# Telemetry_temp_meas.net
KiCad netlist of a schematic drawn in Altium Designer
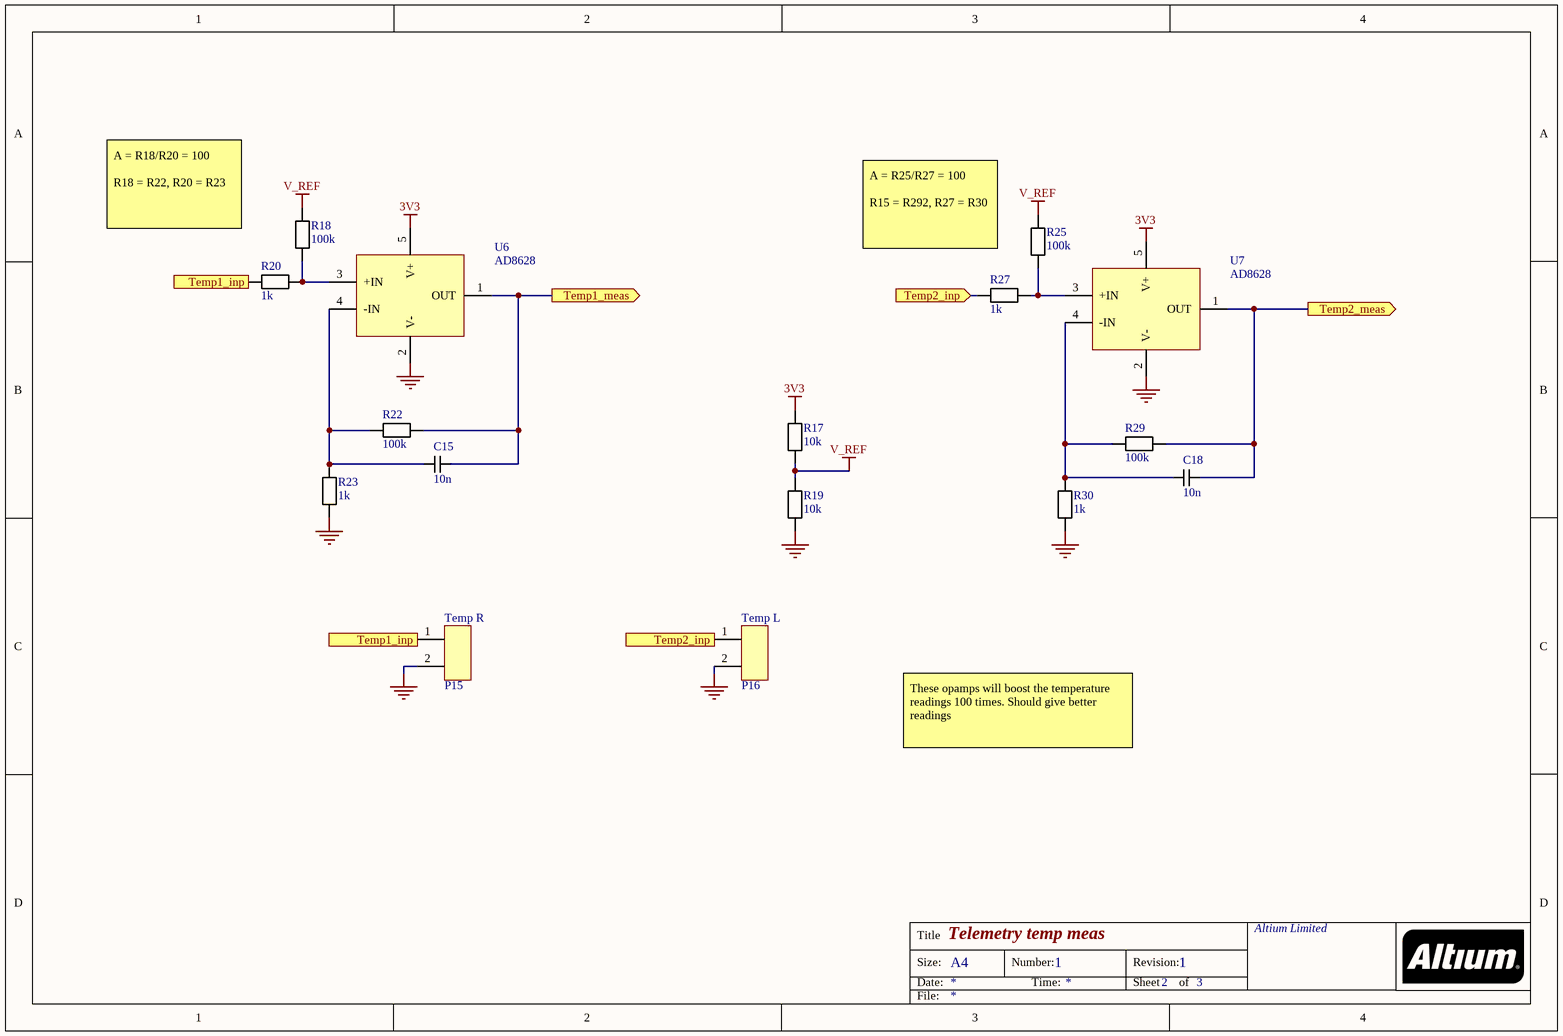
[diagram p0: Telemetry_temp_meas.SchDoc]

(export (version "E")
  (design (tool "Eeschema 10.0.6"))
  (components
    (comp (ref "C15")
      (value "10n")
      (footprint "C_SMD_0805_pcb")
      (fields (field (name "Comment") "SMD"))
      (libsource (lib "FF_component_lib") (part "C_SMD_0805"))
    )
    (comp (ref "C18")
      (value "10n")
      (footprint "C_SMD_0805_pcb")
      (fields (field (name "Comment") "SMD"))
      (libsource (lib "FF_component_lib") (part "C_SMD_0805"))
    )
    (comp (ref "P15")
      (value "Temp R")
      (footprint "JST_SE_2PIN")
      (libsource (lib "FF_component_lib") (part "JST_SE_2PIN"))
    )
    (comp (ref "P16")
      (value "Temp L")
      (footprint "JST_SE_2PIN")
      (libsource (lib "FF_component_lib") (part "JST_SE_2PIN"))
    )
    (comp (ref "R17")
      (value "10k")
      (footprint "R_SMD_0805_pcb")
      (fields (field (name "Comment") "SMD"))
      (libsource (lib "FF_component_lib") (part "R_SMD_0805"))
    )
    (comp (ref "R18")
      (value "100k")
      (footprint "R_SMD_0805_pcb")
      (fields (field (name "Comment") "SMD"))
      (libsource (lib "FF_component_lib") (part "R_SMD_0805"))
    )
    (comp (ref "R19")
      (value "10k")
      (footprint "R_SMD_0805_pcb")
      (fields (field (name "Comment") "SMD"))
      (libsource (lib "FF_component_lib") (part "R_SMD_0805"))
    )
    (comp (ref "R20")
      (value "1k")
      (footprint "R_SMD_0805_pcb")
      (fields (field (name "Comment") "SMD"))
      (libsource (lib "FF_component_lib") (part "R_SMD_0805"))
    )
    (comp (ref "R22")
      (value "100k")
      (footprint "R_SMD_0805_pcb")
      (fields (field (name "Comment") "SMD"))
      (libsource (lib "FF_component_lib") (part "R_SMD_0805"))
    )
    (comp (ref "R23")
      (value "1k")
      (footprint "R_SMD_0805_pcb")
      (fields (field (name "Comment") "SMD"))
      (libsource (lib "FF_component_lib") (part "R_SMD_0805"))
    )
    (comp (ref "R25")
      (value "100k")
      (footprint "R_SMD_0805_pcb")
      (fields (field (name "Comment") "SMD"))
      (libsource (lib "FF_component_lib") (part "R_SMD_0805"))
    )
    (comp (ref "R27")
      (value "1k")
      (footprint "R_SMD_0805_pcb")
      (fields (field (name "Comment") "SMD"))
      (libsource (lib "FF_component_lib") (part "R_SMD_0805"))
    )
    (comp (ref "R29")
      (value "100k")
      (footprint "R_SMD_0805_pcb")
      (fields (field (name "Comment") "SMD"))
      (libsource (lib "FF_component_lib") (part "R_SMD_0805"))
    )
    (comp (ref "R30")
      (value "1k")
      (footprint "R_SMD_0805_pcb")
      (fields (field (name "Comment") "SMD"))
      (libsource (lib "FF_component_lib") (part "R_SMD_0805"))
    )
    (comp (ref "U6")
      (value "AD8628")
      (footprint "SOT-23-5")
      (libsource (lib "FF_component_lib") (part "AD8628WAUJZ-R7_SOT-23-5"))
    )
    (comp (ref "U7")
      (value "AD8628")
      (footprint "SOT-23-5")
      (libsource (lib "FF_component_lib") (part "AD8628WAUJZ-R7_SOT-23-5"))
    )
  )
  (nets
    (net (code "1") (name "/Temp1_inp") (class "Default")
      (node (ref "P15") (pin "1") (pinfunction "1_1") (pintype "passive"))
      (node (ref "R20") (pin "1") (pinfunction "1_1") (pintype "passive"))
    )
    (net (code "2") (name "/Temp1_meas") (class "Default")
      (node (ref "C15") (pin "1") (pinfunction "1_1") (pintype "passive"))
      (node (ref "R22") (pin "2") (pinfunction "2_2") (pintype "passive"))
      (node (ref "U6") (pin "1") (pinfunction "OUT_1") (pintype "passive"))
    )
    (net (code "3") (name "/Temp2_inp") (class "Default")
      (node (ref "P16") (pin "1") (pinfunction "1_1") (pintype "passive"))
      (node (ref "R27") (pin "1") (pinfunction "1_1") (pintype "passive"))
    )
    (net (code "4") (name "/Temp2_meas") (class "Default")
      (node (ref "C18") (pin "1") (pinfunction "1_1") (pintype "passive"))
      (node (ref "R29") (pin "2") (pinfunction "2_2") (pintype "passive"))
      (node (ref "U7") (pin "1") (pinfunction "OUT_1") (pintype "passive"))
    )
    (net (code "5") (name "3V3") (class "Default")
      (node (ref "R17") (pin "2") (pinfunction "2_2") (pintype "passive"))
      (node (ref "U6") (pin "5") (pinfunction "V+_5") (pintype "passive"))
      (node (ref "U7") (pin "5") (pinfunction "V+_5") (pintype "passive"))
    )
    (net (code "6") (name "GND") (class "Default")
      (node (ref "P15") (pin "2") (pinfunction "2_2") (pintype "passive"))
      (node (ref "P16") (pin "2") (pinfunction "2_2") (pintype "passive"))
      (node (ref "R19") (pin "1") (pinfunction "1_1") (pintype "passive"))
      (node (ref "R23") (pin "1") (pinfunction "1_1") (pintype "passive"))
      (node (ref "R30") (pin "2") (pinfunction "2_2") (pintype "passive"))
      (node (ref "U6") (pin "2") (pinfunction "V-_2") (pintype "passive"))
      (node (ref "U7") (pin "2") (pinfunction "V-_2") (pintype "passive"))
    )
    (net (code "7") (name "Net-(U6-+IN)") (class "Default")
      (node (ref "R18") (pin "1") (pinfunction "1_1") (pintype "passive"))
      (node (ref "R20") (pin "2") (pinfunction "2_2") (pintype "passive"))
      (node (ref "U6") (pin "3") (pinfunction "+IN_3") (pintype "passive"))
    )
    (net (code "8") (name "Net-(U6--IN)") (class "Default")
      (node (ref "C15") (pin "2") (pinfunction "2_2") (pintype "passive"))
      (node (ref "R22") (pin "1") (pinfunction "1_1") (pintype "passive"))
      (node (ref "R23") (pin "2") (pinfunction "2_2") (pintype "passive"))
      (node (ref "U6") (pin "4") (pinfunction "-IN_4") (pintype "passive"))
    )
    (net (code "9") (name "Net-(U7-+IN)") (class "Default")
      (node (ref "R25") (pin "1") (pinfunction "1_1") (pintype "passive"))
      (node (ref "R27") (pin "2") (pinfunction "2_2") (pintype "passive"))
      (node (ref "U7") (pin "3") (pinfunction "+IN_3") (pintype "passive"))
    )
    (net (code "10") (name "Net-(U7--IN)") (class "Default")
      (node (ref "C18") (pin "2") (pinfunction "2_2") (pintype "passive"))
      (node (ref "R29") (pin "1") (pinfunction "1_1") (pintype "passive"))
      (node (ref "R30") (pin "1") (pinfunction "1_1") (pintype "passive"))
      (node (ref "U7") (pin "4") (pinfunction "-IN_4") (pintype "passive"))
    )
    (net (code "11") (name "V_REF") (class "Default")
      (node (ref "R17") (pin "1") (pinfunction "1_1") (pintype "passive"))
      (node (ref "R18") (pin "2") (pinfunction "2_2") (pintype "passive"))
      (node (ref "R19") (pin "2") (pinfunction "2_2") (pintype "passive"))
      (node (ref "R25") (pin "2") (pinfunction "2_2") (pintype "passive"))
    )
  )
)
